# Sheet1.net
KiCad netlist of a schematic drawn in Altium Designer
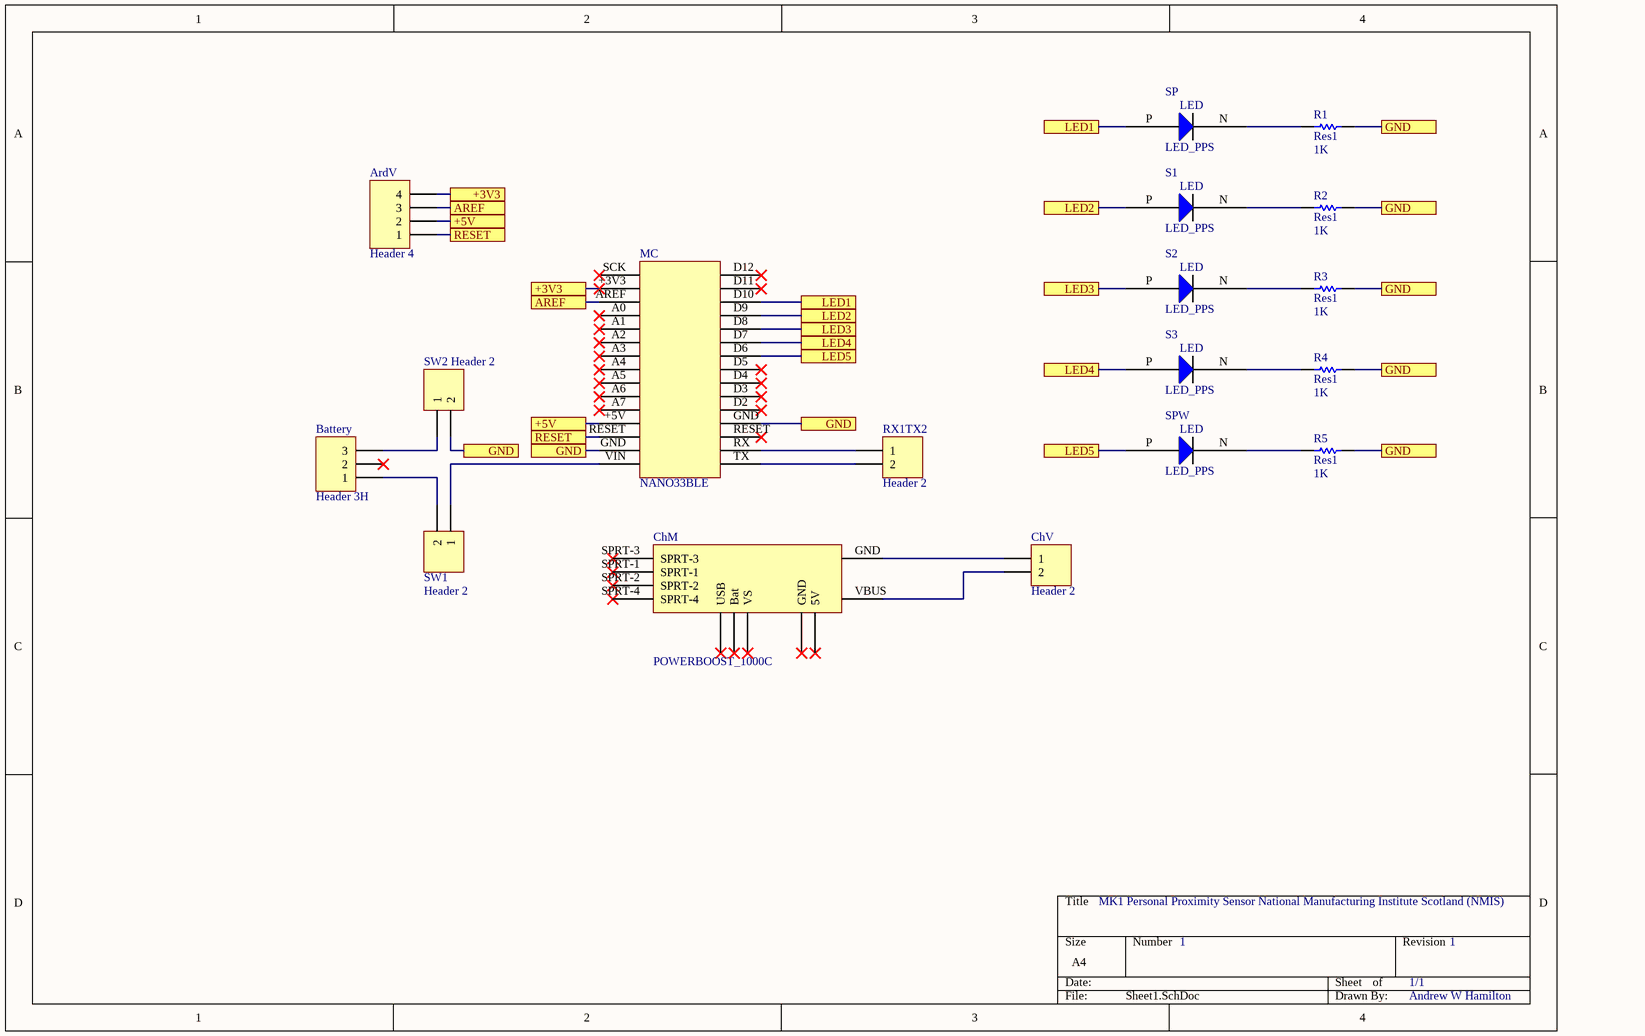
[diagram p0: Sheet1.SchDoc]

(export (version "E")
  (design (tool "Eeschema 10.0.6"))
  (components
    (comp (ref "ArdV")
      (value "Header 4")
      (footprint "HDR1X4")
      (description "Header, 4-Pin")
      (fields (field (name "PUBLISHER") "Altium Limited"))
      (libsource (lib "Miscellaneous Connectors") (part "Header 4"))
    )
    (comp (ref "Battery")
      (value "Header 3H")
      (footprint "HDR1X3H")
      (description "Header, 3-Pin, Right Angle")
      (fields (field (name "PUBLISHER") "Altium Limited"))
      (libsource (lib "Miscellaneous Connectors") (part "Header 3H"))
    )
    (comp (ref "ChM")
      (value "POWERBOOST_1000C")
      (footprint "POWERBOOST_1000C")
      (libsource (lib "RTD") (part "POWERBOOST_1000C"))
    )
    (comp (ref "ChV")
      (value "Header 2")
      (footprint "HDR1X2")
      (description "Header, 2-Pin")
      (fields (field (name "PUBLISHER") "Altium Limited"))
      (libsource (lib "Miscellaneous Connectors") (part "Header 2"))
    )
    (comp (ref "MC")
      (value "NANO33BLE")
      (footprint "ARDUINO_NANO_BLE_33")
      (libsource (lib "RTD") (part "NANO33BLE"))
    )
    (comp (ref "R1")
      (value "Res1")
      (footprint "AXIAL-0.3")
      (description "Resistor")
      (fields (field (name "ALTIUM_VALUE") "1K") (field (name "PUBLISHER") "Altium Limited"))
      (libsource (lib "Miscellaneous Devices") (part "Res1"))
    )
    (comp (ref "R2")
      (value "Res1")
      (footprint "AXIAL-0.3")
      (description "Resistor")
      (fields (field (name "ALTIUM_VALUE") "1K") (field (name "PUBLISHER") "Altium Limited"))
      (libsource (lib "Miscellaneous Devices") (part "Res1"))
    )
    (comp (ref "R3")
      (value "Res1")
      (footprint "AXIAL-0.3")
      (description "Resistor")
      (fields (field (name "ALTIUM_VALUE") "1K") (field (name "PUBLISHER") "Altium Limited"))
      (libsource (lib "Miscellaneous Devices") (part "Res1"))
    )
    (comp (ref "R4")
      (value "Res1")
      (footprint "AXIAL-0.3")
      (description "Resistor")
      (fields (field (name "ALTIUM_VALUE") "1K") (field (name "PUBLISHER") "Altium Limited"))
      (libsource (lib "Miscellaneous Devices") (part "Res1"))
    )
    (comp (ref "R5")
      (value "Res1")
      (footprint "AXIAL-0.3")
      (description "Resistor")
      (fields (field (name "ALTIUM_VALUE") "1K") (field (name "PUBLISHER") "Altium Limited"))
      (libsource (lib "Miscellaneous Devices") (part "Res1"))
    )
    (comp (ref "RX1TX2")
      (value "Header 2")
      (footprint "HDR1X2")
      (description "Header, 2-Pin")
      (fields (field (name "PUBLISHER") "Altium Limited"))
      (libsource (lib "Miscellaneous Connectors") (part "Header 2"))
    )
    (comp (ref "S1") (value "LED_PPS") (footprint "LED_PPS") (libsource (lib "RTD") (part "LED_PPS")))
    (comp (ref "S2") (value "LED_PPS") (footprint "LED_PPS") (libsource (lib "RTD") (part "LED_PPS")))
    (comp (ref "S3") (value "LED_PPS") (footprint "LED_PPS") (libsource (lib "RTD") (part "LED_PPS")))
    (comp (ref "SP") (value "LED_PPS") (footprint "LED_PPS") (libsource (lib "RTD") (part "LED_PPS")))
    (comp (ref "SPW") (value "LED_PPS") (footprint "LED_PPS") (libsource (lib "RTD") (part "LED_PPS")))
    (comp (ref "SW1")
      (value "Header 2")
      (footprint "HDR1X2")
      (description "Header, 2-Pin")
      (fields (field (name "PUBLISHER") "Altium Limited"))
      (libsource (lib "") (part "Header 2_2"))
    )
    (comp (ref "SW2")
      (value "Header 2")
      (footprint "HDR1X2")
      (description "Header, 2-Pin")
      (fields (field (name "PUBLISHER") "Altium Limited"))
      (libsource (lib "") (part "Header 2_1"))
    )
  )
  (nets
    (net (code "1") (name "/+3V3") (class "Default")
      (node (ref "ArdV") (pin "4") (pinfunction "4_4") (pintype "passive"))
      (node (ref "MC") (pin "+3V3") (pinfunction "2_+3V3") (pintype "passive"))
    )
    (net (code "2") (name "/+5V") (class "Default")
      (node (ref "ArdV") (pin "2") (pinfunction "2_2") (pintype "passive"))
      (node (ref "MC") (pin "+5V") (pinfunction "12_+5V") (pintype "passive"))
    )
    (net (code "3") (name "/AREF") (class "Default")
      (node (ref "ArdV") (pin "3") (pinfunction "3_3") (pintype "passive"))
      (node (ref "MC") (pin "AREF") (pinfunction "3_AREF") (pintype "passive"))
    )
    (net (code "4") (name "/GND") (class "Default")
      (node (ref "MC") (pin "GND") (pinfunction "14_GND") (pintype "passive"))
      (node (ref "R1") (pin "2") (pinfunction "2_2") (pintype "passive"))
      (node (ref "R2") (pin "2") (pinfunction "2_2") (pintype "passive"))
      (node (ref "R3") (pin "2") (pinfunction "2_2") (pintype "passive"))
      (node (ref "R4") (pin "2") (pinfunction "2_2") (pintype "passive"))
      (node (ref "R5") (pin "2") (pinfunction "2_2") (pintype "passive"))
      (node (ref "SW2") (pin "2") (pinfunction "2_2") (pintype "passive"))
    )
    (net (code "5") (name "/LED1") (class "Default")
      (node (ref "MC") (pin "D10") (pinfunction "18_D10") (pintype "passive"))
      (node (ref "SP") (pin "P") (pinfunction "0_P") (pintype "passive"))
    )
    (net (code "6") (name "/LED2") (class "Default")
      (node (ref "MC") (pin "D9") (pinfunction "19_D9") (pintype "passive"))
      (node (ref "S1") (pin "P") (pinfunction "0_P") (pintype "passive"))
    )
    (net (code "7") (name "/LED3") (class "Default")
      (node (ref "MC") (pin "D8") (pinfunction "20_D8") (pintype "passive"))
      (node (ref "S2") (pin "P") (pinfunction "0_P") (pintype "passive"))
    )
    (net (code "8") (name "/LED4") (class "Default")
      (node (ref "MC") (pin "D7") (pintype "passive"))
      (node (ref "S3") (pin "P") (pinfunction "0_P") (pintype "passive"))
    )
    (net (code "9") (name "/LED5") (class "Default")
      (node (ref "MC") (pin "D6") (pinfunction "22_D6") (pintype "passive"))
      (node (ref "SPW") (pin "P") (pinfunction "0_P") (pintype "passive"))
    )
    (net (code "10") (name "/RESET") (class "Default")
      (node (ref "ArdV") (pin "1") (pinfunction "1_1") (pintype "passive"))
      (node (ref "MC") (pin "RESET") (pinfunction "13_RESET") (pintype "passive"))
    )
    (net (code "11") (name "Net-(Battery-Pad1)") (class "Default")
      (node (ref "Battery") (pin "1") (pinfunction "1_1") (pintype "passive"))
      (node (ref "SW1") (pin "2") (pinfunction "2_2") (pintype "passive"))
    )
    (net (code "12") (name "Net-(Battery-Pad3)") (class "Default")
      (node (ref "Battery") (pin "3") (pinfunction "3_3") (pintype "passive"))
      (node (ref "SW2") (pin "1") (pinfunction "1_1") (pintype "passive"))
    )
    (net (code "13") (name "Net-(ChM-PadGND)") (class "Default")
      (node (ref "ChM") (pin "GND") (pinfunction "GND_GND") (pintype "passive"))
      (node (ref "ChV") (pin "1") (pinfunction "1_1") (pintype "passive"))
    )
    (net (code "14") (name "Net-(ChM-PadVBUS)") (class "Default")
      (node (ref "ChM") (pin "VBUS") (pinfunction "VBUS_VBUS") (pintype "passive"))
      (node (ref "ChV") (pin "2") (pinfunction "2_2") (pintype "passive"))
    )
    (net (code "15") (name "Net-(MC-15)") (class "Default")
      (node (ref "MC") (pin "VIN") (pinfunction "15_VIN") (pintype "passive"))
      (node (ref "SW1") (pin "1") (pinfunction "1_1") (pintype "passive"))
    )
    (net (code "16") (name "Net-(MC-29)") (class "Default")
      (node (ref "MC") (pin "RX") (pinfunction "29_RX") (pintype "passive"))
      (node (ref "RX1TX2") (pin "1") (pinfunction "1_1") (pintype "passive"))
    )
    (net (code "17") (name "Net-(MC-30)") (class "Default")
      (node (ref "MC") (pin "TX") (pinfunction "30_TX") (pintype "passive"))
      (node (ref "RX1TX2") (pin "2") (pinfunction "2_2") (pintype "passive"))
    )
    (net (code "18") (name "Net-(S1-1)") (class "Default")
      (node (ref "R2") (pin "1") (pinfunction "1_1") (pintype "passive"))
      (node (ref "S1") (pin "N") (pinfunction "1_N") (pintype "passive"))
    )
    (net (code "19") (name "Net-(S2-1)") (class "Default")
      (node (ref "R3") (pin "1") (pinfunction "1_1") (pintype "passive"))
      (node (ref "S2") (pin "N") (pinfunction "1_N") (pintype "passive"))
    )
    (net (code "20") (name "Net-(S3-1)") (class "Default")
      (node (ref "R4") (pin "1") (pinfunction "1_1") (pintype "passive"))
      (node (ref "S3") (pin "N") (pinfunction "1_N") (pintype "passive"))
    )
    (net (code "21") (name "Net-(SP-1)") (class "Default")
      (node (ref "R1") (pin "1") (pinfunction "1_1") (pintype "passive"))
      (node (ref "SP") (pin "N") (pinfunction "1_N") (pintype "passive"))
    )
    (net (code "22") (name "Net-(SPW-1)") (class "Default")
      (node (ref "R5") (pin "1") (pinfunction "1_1") (pintype "passive"))
      (node (ref "SPW") (pin "N") (pinfunction "1_N") (pintype "passive"))
    )
    (net (code "23") (name "unconnected-(Battery-Pad2)") (class "Default")
      (node (ref "Battery") (pin "2") (pinfunction "2_2") (pintype "passive+no_connect"))
    )
    (net (code "24") (name "unconnected-(ChM-Pad5V)") (class "Default")
      (node (ref "ChM") (pin "5V") (pinfunction "5V_5V") (pintype "passive+no_connect"))
    )
    (net (code "25") (name "unconnected-(ChM-PadBat)") (class "Default")
      (node (ref "ChM") (pin "Bat") (pinfunction "Bat_Bat") (pintype "passive+no_connect"))
    )
    (net (code "26") (name "unconnected-(ChM-PadGND)") (class "Default")
      (node (ref "ChM") (pin "GND") (pinfunction "GND_GND") (pintype "passive+no_connect"))
    )
    (net (code "27") (name "unconnected-(ChM-PadSPRT-1)") (class "Default")
      (node (ref "ChM") (pin "SPRT-1") (pinfunction "SPRT-1_SPRT-1") (pintype "passive+no_connect"))
    )
    (net (code "28") (name "unconnected-(ChM-PadSPRT-2)") (class "Default")
      (node (ref "ChM") (pin "SPRT-2") (pinfunction "SPRT-2_SPRT-2") (pintype "passive+no_connect"))
    )
    (net (code "29") (name "unconnected-(ChM-PadSPRT-3)") (class "Default")
      (node (ref "ChM") (pin "SPRT-3") (pinfunction "SPRT-3_SPRT-3") (pintype "passive+no_connect"))
    )
    (net (code "30") (name "unconnected-(ChM-PadSPRT-4)") (class "Default")
      (node (ref "ChM") (pin "SPRT-4") (pinfunction "SPRT-4_SPRT-4") (pintype "passive+no_connect"))
    )
    (net (code "31") (name "unconnected-(ChM-PadUSB)") (class "Default")
      (node (ref "ChM") (pin "USB") (pinfunction "USB_USB") (pintype "passive+no_connect"))
    )
    (net (code "32") (name "unconnected-(ChM-PadVS)") (class "Default")
      (node (ref "ChM") (pin "VS") (pinfunction "VS_VS") (pintype "passive+no_connect"))
    )
    (net (code "33") (name "unconnected-(MC-1-PadSCK)") (class "Default")
      (node (ref "MC") (pin "SCK") (pinfunction "1_SCK") (pintype "passive+no_connect"))
    )
    (net (code "34") (name "unconnected-(MC-4-PadA0)") (class "Default")
      (node (ref "MC") (pin "A0") (pinfunction "4_A0") (pintype "passive+no_connect"))
    )
    (net (code "35") (name "unconnected-(MC-5-PadA1)") (class "Default")
      (node (ref "MC") (pin "A1") (pinfunction "5_A1") (pintype "passive+no_connect"))
    )
    (net (code "36") (name "unconnected-(MC-6-PadA2)") (class "Default")
      (node (ref "MC") (pin "A2") (pinfunction "6_A2") (pintype "passive+no_connect"))
    )
    (net (code "37") (name "unconnected-(MC-7-PadA3)") (class "Default")
      (node (ref "MC") (pin "A3") (pinfunction "7_A3") (pintype "passive+no_connect"))
    )
    (net (code "38") (name "unconnected-(MC-8-PadA4)") (class "Default")
      (node (ref "MC") (pin "A4") (pinfunction "8_A4") (pintype "passive+no_connect"))
    )
    (net (code "39") (name "unconnected-(MC-9-PadA5)") (class "Default")
      (node (ref "MC") (pin "A5") (pinfunction "9_A5") (pintype "passive+no_connect"))
    )
    (net (code "40") (name "unconnected-(MC-10-PadA6)") (class "Default")
      (node (ref "MC") (pin "A6") (pinfunction "10_A6") (pintype "passive+no_connect"))
    )
    (net (code "41") (name "unconnected-(MC-11-PadA7)") (class "Default")
      (node (ref "MC") (pin "A7") (pinfunction "11_A7") (pintype "passive+no_connect"))
    )
    (net (code "42") (name "unconnected-(MC-16-PadD12)") (class "Default")
      (node (ref "MC") (pin "D12") (pinfunction "16_D12") (pintype "passive+no_connect"))
    )
    (net (code "43") (name "unconnected-(MC-23-PadD5)") (class "Default")
      (node (ref "MC") (pin "D5") (pinfunction "23_D5") (pintype "passive+no_connect"))
    )
    (net (code "44") (name "unconnected-(MC-24-PadD4)") (class "Default")
      (node (ref "MC") (pin "D4") (pinfunction "24_D4") (pintype "passive+no_connect"))
    )
    (net (code "45") (name "unconnected-(MC-25-PadD3)") (class "Default")
      (node (ref "MC") (pin "D3") (pinfunction "25_D3") (pintype "passive+no_connect"))
    )
    (net (code "46") (name "unconnected-(MC-26-PadD2)") (class "Default")
      (node (ref "MC") (pin "D2") (pinfunction "26_D2") (pintype "passive+no_connect"))
    )
    (net (code "47") (name "unconnected-(MC-28-PadRESET)") (class "Default")
      (node (ref "MC") (pin "RESET") (pinfunction "28_RESET") (pintype "passive+no_connect"))
    )
    (net (code "48") (name "unconnected-(MC-PadD11)") (class "Default")
      (node (ref "MC") (pin "D11") (pintype "passive+no_connect"))
    )
  )
)
